# controller.net
KiCad netlist of a schematic drawn in EAGLE
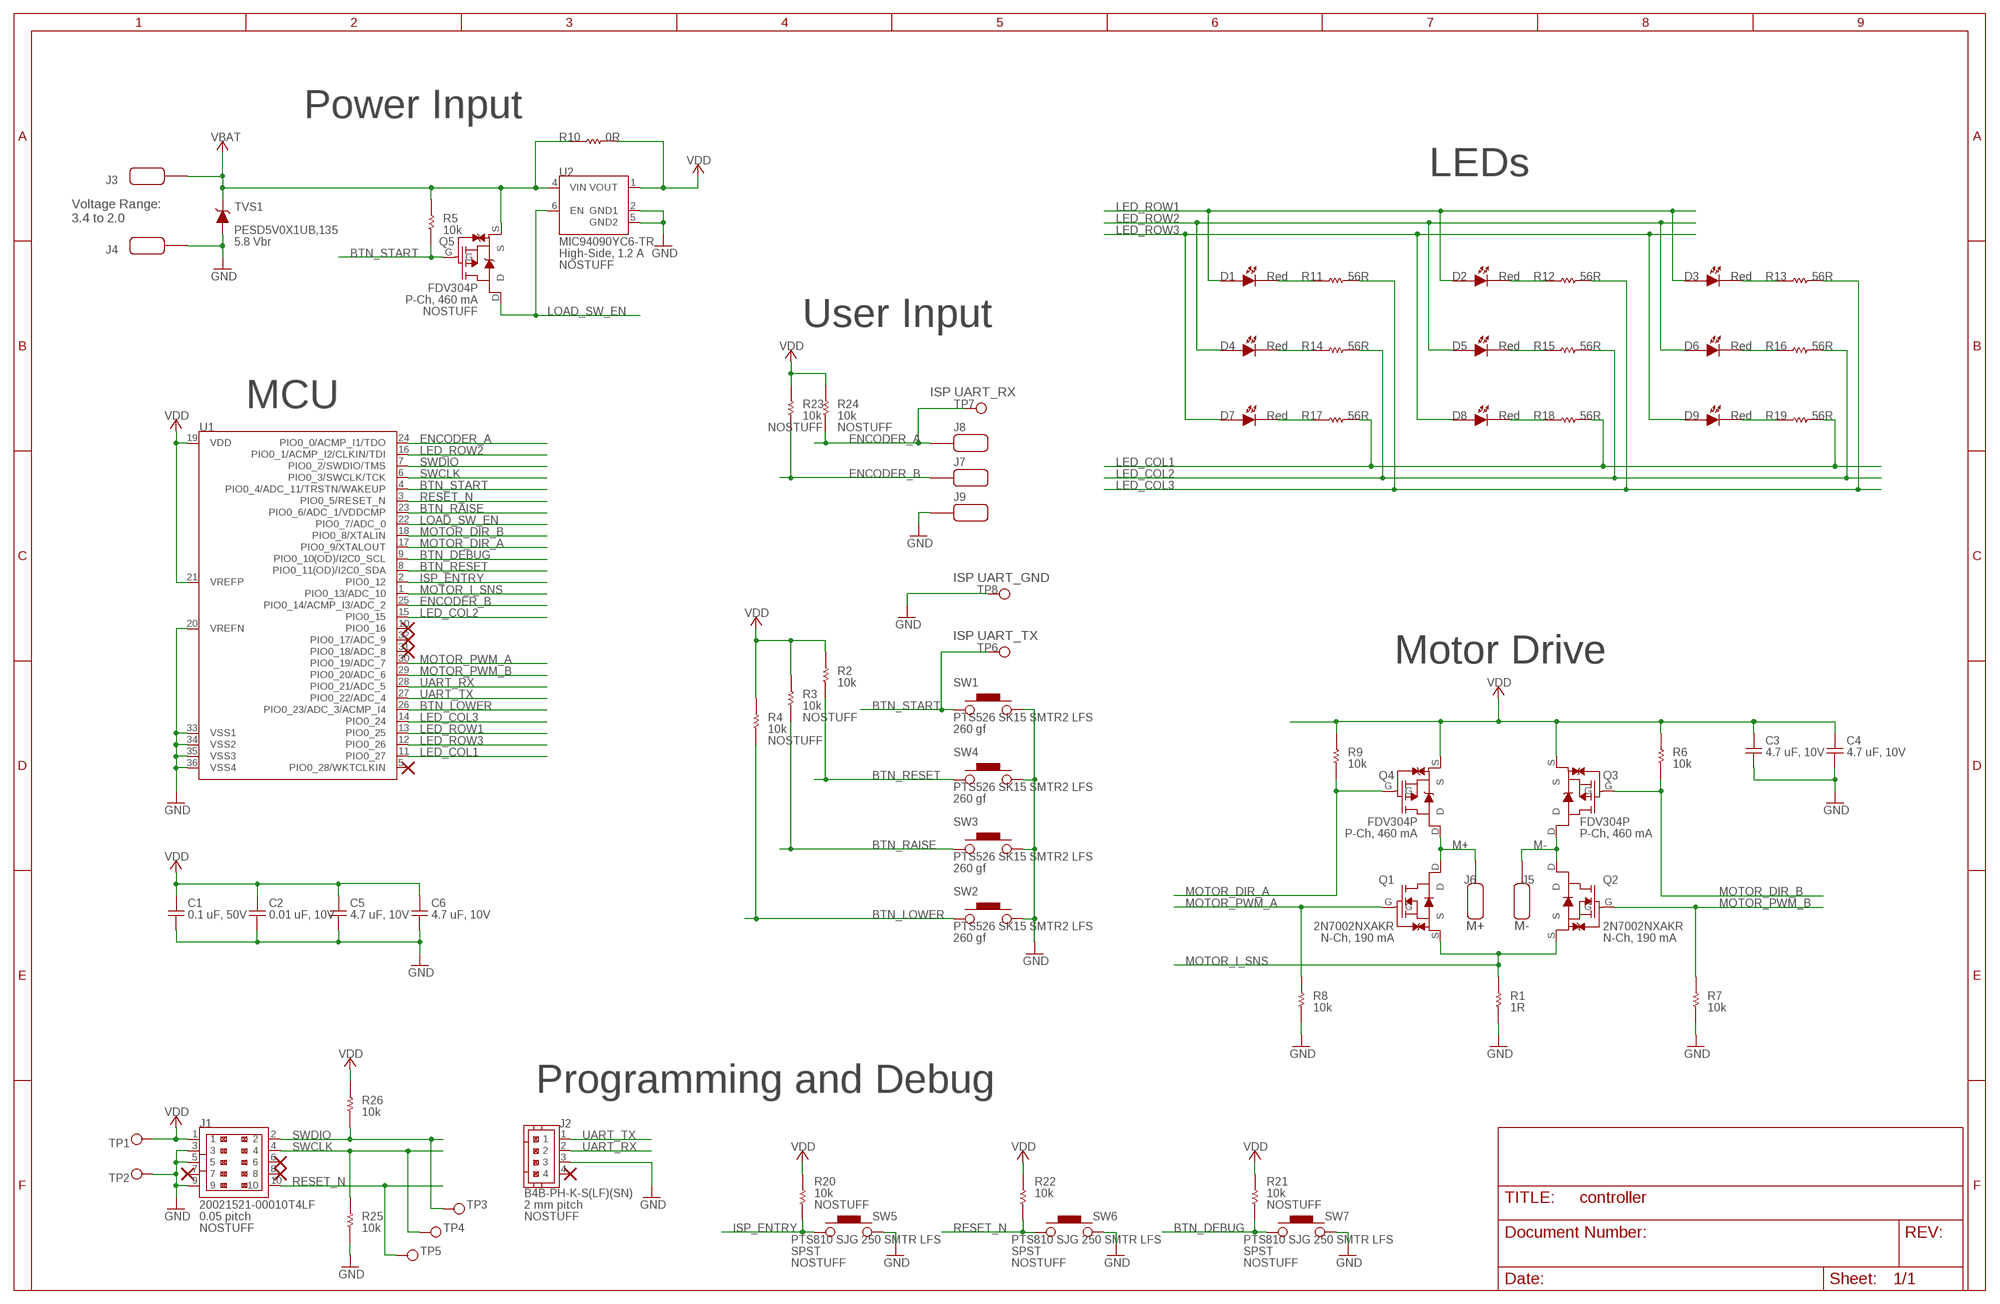
[diagram p0: schematic, sheet 1]

(export (version "E")
  (design (tool "Eeschema 10.0.6"))
  (components
    (comp (ref "C1")
      (value "CAP_C1608X7R1H104K080AA")
      (footprint "eagle-import:CAP_0603")
      (fields
        (field (name "DISPLAY") "0.1 uF, 50V")
        (field (name "DIST_PART_NO") "445-1314-1-ND")
        (field (name "MFG") "TDK")
        (field (name "MFG_PART_NO") "C1608X7R1H104K080AA")
      )
      (libsource (lib "eagle-import") (part "CAP_C1608X7R1H104K080AA"))
    )
    (comp (ref "C2")
      (value "CAP_CL10B103KB8NNNC")
      (footprint "eagle-import:CAP_0603")
      (fields
        (field (name "DISPLAY") "0.01 uF, 10V")
        (field (name "DIST_PART_NO") "1276-1009-1-ND")
        (field (name "MFG") "Samsung")
        (field (name "MFG_PART_NO") "CL10B103KB8NNNC")
      )
      (libsource (lib "eagle-import") (part "CAP_CL10B103KB8NNNC"))
    )
    (comp (ref "C3")
      (value "CAP_CGB3B1X5R1A475M055AC")
      (footprint "eagle-import:CAP_0603")
      (fields
        (field (name "DISPLAY") "4.7 uF, 10V")
        (field (name "DIST_PART_NO") "445-7483-1-ND")
        (field (name "MFG") "TDK")
        (field (name "MFG_PART_NO") "CGB3B1X5R1A475M055AC")
      )
      (libsource (lib "eagle-import") (part "CAP_CGB3B1X5R1A475M055AC"))
    )
    (comp (ref "C4")
      (value "CAP_CGB3B1X5R1A475M055AC")
      (footprint "eagle-import:CAP_0603")
      (fields
        (field (name "DISPLAY") "4.7 uF, 10V")
        (field (name "DIST_PART_NO") "445-7483-1-ND")
        (field (name "MFG") "TDK")
        (field (name "MFG_PART_NO") "CGB3B1X5R1A475M055AC")
      )
      (libsource (lib "eagle-import") (part "CAP_CGB3B1X5R1A475M055AC"))
    )
    (comp (ref "C5")
      (value "CAP_CGB3B1X5R1A475M055AC")
      (footprint "eagle-import:CAP_0603")
      (fields
        (field (name "DISPLAY") "4.7 uF, 10V")
        (field (name "DIST_PART_NO") "445-7483-1-ND")
        (field (name "MFG") "TDK")
        (field (name "MFG_PART_NO") "CGB3B1X5R1A475M055AC")
      )
      (libsource (lib "eagle-import") (part "CAP_CGB3B1X5R1A475M055AC"))
    )
    (comp (ref "C6")
      (value "CAP_CGB3B1X5R1A475M055AC")
      (footprint "eagle-import:CAP_0603")
      (fields
        (field (name "DISPLAY") "4.7 uF, 10V")
        (field (name "DIST_PART_NO") "445-7483-1-ND")
        (field (name "MFG") "TDK")
        (field (name "MFG_PART_NO") "CGB3B1X5R1A475M055AC")
      )
      (libsource (lib "eagle-import") (part "CAP_CGB3B1X5R1A475M055AC"))
    )
    (comp (ref "D1")
      (value "LED_150060RS75000")
      (footprint "eagle-import:LED_0603")
      (fields
        (field (name "DISPLAY") "Red")
        (field (name "DIST_PART_NO") "732-4978-1-ND")
        (field (name "MFG") "Wurth Elektronik")
        (field (name "MFG_PART_NO") "150060RS75000")
      )
      (libsource (lib "eagle-import") (part "LED_150060RS75000"))
    )
    (comp (ref "D2")
      (value "LED_150060RS75000")
      (footprint "eagle-import:LED_0603")
      (fields
        (field (name "DISPLAY") "Red")
        (field (name "DIST_PART_NO") "732-4978-1-ND")
        (field (name "MFG") "Wurth Elektronik")
        (field (name "MFG_PART_NO") "150060RS75000")
      )
      (libsource (lib "eagle-import") (part "LED_150060RS75000"))
    )
    (comp (ref "D3")
      (value "LED_150060RS75000")
      (footprint "eagle-import:LED_0603")
      (fields
        (field (name "DISPLAY") "Red")
        (field (name "DIST_PART_NO") "732-4978-1-ND")
        (field (name "MFG") "Wurth Elektronik")
        (field (name "MFG_PART_NO") "150060RS75000")
      )
      (libsource (lib "eagle-import") (part "LED_150060RS75000"))
    )
    (comp (ref "D4")
      (value "LED_150060RS75000")
      (footprint "eagle-import:LED_0603")
      (fields
        (field (name "DISPLAY") "Red")
        (field (name "DIST_PART_NO") "732-4978-1-ND")
        (field (name "MFG") "Wurth Elektronik")
        (field (name "MFG_PART_NO") "150060RS75000")
      )
      (libsource (lib "eagle-import") (part "LED_150060RS75000"))
    )
    (comp (ref "D5")
      (value "LED_150060RS75000")
      (footprint "eagle-import:LED_0603")
      (fields
        (field (name "DISPLAY") "Red")
        (field (name "DIST_PART_NO") "732-4978-1-ND")
        (field (name "MFG") "Wurth Elektronik")
        (field (name "MFG_PART_NO") "150060RS75000")
      )
      (libsource (lib "eagle-import") (part "LED_150060RS75000"))
    )
    (comp (ref "D6")
      (value "LED_150060RS75000")
      (footprint "eagle-import:LED_0603")
      (fields
        (field (name "DISPLAY") "Red")
        (field (name "DIST_PART_NO") "732-4978-1-ND")
        (field (name "MFG") "Wurth Elektronik")
        (field (name "MFG_PART_NO") "150060RS75000")
      )
      (libsource (lib "eagle-import") (part "LED_150060RS75000"))
    )
    (comp (ref "D7")
      (value "LED_150060RS75000")
      (footprint "eagle-import:LED_0603")
      (fields
        (field (name "DISPLAY") "Red")
        (field (name "DIST_PART_NO") "732-4978-1-ND")
        (field (name "MFG") "Wurth Elektronik")
        (field (name "MFG_PART_NO") "150060RS75000")
      )
      (libsource (lib "eagle-import") (part "LED_150060RS75000"))
    )
    (comp (ref "D8")
      (value "LED_150060RS75000")
      (footprint "eagle-import:LED_0603")
      (fields
        (field (name "DISPLAY") "Red")
        (field (name "DIST_PART_NO") "732-4978-1-ND")
        (field (name "MFG") "Wurth Elektronik")
        (field (name "MFG_PART_NO") "150060RS75000")
      )
      (libsource (lib "eagle-import") (part "LED_150060RS75000"))
    )
    (comp (ref "D9")
      (value "LED_150060RS75000")
      (footprint "eagle-import:LED_0603")
      (fields
        (field (name "DISPLAY") "Red")
        (field (name "DIST_PART_NO") "732-4978-1-ND")
        (field (name "MFG") "Wurth Elektronik")
        (field (name "MFG_PART_NO") "150060RS75000")
      )
      (libsource (lib "eagle-import") (part "LED_150060RS75000"))
    )
    (comp (ref "J1")
      (value "20021521-00010T4LF")
      (footprint "eagle-import:HEADER_2X5_50MIL_SHROUDED_KEYED")
      (fields
        (field (name "MFG_PART_NO") "20021521-00010T4LF")
        (field (name "DISPLAY") "0.05 pitch")
        (field (name "DIST_PART_NO") "609-6534-ND")
        (field (name "MFG") "Amphenol")
        (field (name "NOSTUFF") "NOSTUFF")
      )
      (libsource (lib "eagle-import") (part "20021521-00010T4LF"))
    )
    (comp (ref "J2")
      (value "B4B-PH-K-S")
      (footprint "eagle-import:JST-PH_2MM_TH")
      (fields
        (field (name "MFG_PART_NO") "B4B-PH-K-S(LF)(SN)")
        (field (name "DISPLAY") "2 mm pitch")
        (field (name "DIST_PART_NO") "455-1706-ND")
        (field (name "MFG") "JST")
        (field (name "NOSTUFF") "NOSTUFF")
      )
      (libsource (lib "eagle-import") (part "B4B-PH-K-S"))
    )
    (comp (ref "J3")
      (value "PAD_1P4X3P25MM")
      (footprint "eagle-import:PAD_1P4MM_X_3P25MM")
      (libsource (lib "eagle-import") (part "PAD_1P4X3P25MM"))
    )
    (comp (ref "J4")
      (value "PAD_1P4X3P25MM")
      (footprint "eagle-import:PAD_1P4MM_X_3P25MM")
      (libsource (lib "eagle-import") (part "PAD_1P4X3P25MM"))
    )
    (comp (ref "J5")
      (value "PAD_1P4X3P25MM")
      (footprint "eagle-import:PAD_1P4MM_X_3P25MM")
      (libsource (lib "eagle-import") (part "PAD_1P4X3P25MM"))
    )
    (comp (ref "J6")
      (value "PAD_1P4X3P25MM")
      (footprint "eagle-import:PAD_1P4MM_X_3P25MM")
      (libsource (lib "eagle-import") (part "PAD_1P4X3P25MM"))
    )
    (comp (ref "J7")
      (value "PAD_1P4X3P25MM")
      (footprint "eagle-import:PAD_1P4MM_X_3P25MM")
      (libsource (lib "eagle-import") (part "PAD_1P4X3P25MM"))
    )
    (comp (ref "J8")
      (value "PAD_1P4X3P25MM")
      (footprint "eagle-import:PAD_1P4MM_X_3P25MM")
      (libsource (lib "eagle-import") (part "PAD_1P4X3P25MM"))
    )
    (comp (ref "J9")
      (value "PAD_1P4X3P25MM")
      (footprint "eagle-import:PAD_1P4MM_X_3P25MM")
      (libsource (lib "eagle-import") (part "PAD_1P4X3P25MM"))
    )
    (comp (ref "Q1")
      (value "2N7002NXAKR")
      (footprint "eagle-import:SOT-23_FET_GENERIC")
      (fields
        (field (name "DISPLAY") "N-Ch, 190 mA")
        (field (name "MFG_PART_NO") "2N7002NXAKR")
        (field (name "DIST_PART_NO") "1727-8643-1-ND")
        (field (name "MFG") "Nexperia")
      )
      (libsource (lib "eagle-import") (part "2N7002NXAKR"))
    )
    (comp (ref "Q2")
      (value "2N7002NXAKR")
      (footprint "eagle-import:SOT-23_FET_GENERIC")
      (fields
        (field (name "DISPLAY") "N-Ch, 190 mA")
        (field (name "MFG_PART_NO") "2N7002NXAKR")
        (field (name "DIST_PART_NO") "1727-8643-1-ND")
        (field (name "MFG") "Nexperia")
      )
      (libsource (lib "eagle-import") (part "2N7002NXAKR"))
    )
    (comp (ref "Q3")
      (value "FDV304P")
      (footprint "eagle-import:SOT-23_FET_GENERIC")
      (fields
        (field (name "DISPLAY") "P-Ch, 460 mA")
        (field (name "MFG_PART_NO") "FDV304P")
        (field (name "DIST_PART_NO") "FDV304PCT-ND")
        (field (name "MFG") "On Semi")
      )
      (libsource (lib "eagle-import") (part "FDV304P"))
    )
    (comp (ref "Q4")
      (value "FDV304P")
      (footprint "eagle-import:SOT-23_FET_GENERIC")
      (fields
        (field (name "DISPLAY") "P-Ch, 460 mA")
        (field (name "MFG_PART_NO") "FDV304P")
        (field (name "DIST_PART_NO") "FDV304PCT-ND")
        (field (name "MFG") "On Semi")
      )
      (libsource (lib "eagle-import") (part "FDV304P"))
    )
    (comp (ref "Q5")
      (value "FDV304P")
      (footprint "eagle-import:SOT-23_FET_GENERIC")
      (fields
        (field (name "DISPLAY") "P-Ch, 460 mA")
        (field (name "MFG_PART_NO") "FDV304P")
        (field (name "DIST_PART_NO") "FDV304PCT-ND")
        (field (name "MFG") "On Semi")
        (field (name "NOSTUFF") "NOSTUFF")
      )
      (libsource (lib "eagle-import") (part "FDV304P"))
    )
    (comp (ref "R1")
      (value "RES_1R_RMCF0603FT1R00")
      (footprint "eagle-import:RES_0603")
      (fields
        (field (name "DISPLAY") "1R")
        (field (name "DIST_PART_NO") "RMCF0603FT1R00CT-ND")
        (field (name "MFG") "Stackpole")
        (field (name "MFG_PART_NO") "RMCF0603FT1R00")
      )
      (libsource (lib "eagle-import") (part "RES_1R_RMCF0603FT1R00"))
    )
    (comp (ref "R2")
      (value "RES_10K_RC0603FR-0710KL")
      (footprint "eagle-import:RES_0603")
      (fields
        (field (name "DISPLAY") "10k")
        (field (name "DIST_PART_NO") "311-10.0KHRCT-ND")
        (field (name "MFG") "Yageo")
        (field (name "MFG_PART_NO") "RC0603FR-0710KL")
      )
      (libsource (lib "eagle-import") (part "RES_10K_RC0603FR-0710KL"))
    )
    (comp (ref "R3")
      (value "RES_10K_RC0603FR-0710KL")
      (footprint "eagle-import:RES_0603")
      (fields
        (field (name "DISPLAY") "10k")
        (field (name "DIST_PART_NO") "311-10.0KHRCT-ND")
        (field (name "MFG") "Yageo")
        (field (name "MFG_PART_NO") "RC0603FR-0710KL")
        (field (name "NOSTUFF") "NOSTUFF")
      )
      (libsource (lib "eagle-import") (part "RES_10K_RC0603FR-0710KL"))
    )
    (comp (ref "R4")
      (value "RES_10K_RC0603FR-0710KL")
      (footprint "eagle-import:RES_0603")
      (fields
        (field (name "DISPLAY") "10k")
        (field (name "DIST_PART_NO") "311-10.0KHRCT-ND")
        (field (name "MFG") "Yageo")
        (field (name "MFG_PART_NO") "RC0603FR-0710KL")
        (field (name "NOSTUFF") "NOSTUFF")
      )
      (libsource (lib "eagle-import") (part "RES_10K_RC0603FR-0710KL"))
    )
    (comp (ref "R5")
      (value "RES_10K_RC0603FR-0710KL")
      (footprint "eagle-import:RES_0603")
      (fields
        (field (name "DISPLAY") "10k")
        (field (name "DIST_PART_NO") "311-10.0KHRCT-ND")
        (field (name "MFG") "Yageo")
        (field (name "MFG_PART_NO") "RC0603FR-0710KL")
      )
      (libsource (lib "eagle-import") (part "RES_10K_RC0603FR-0710KL"))
    )
    (comp (ref "R6")
      (value "RES_10K_RC0603FR-0710KL")
      (footprint "eagle-import:RES_0603")
      (fields
        (field (name "DISPLAY") "10k")
        (field (name "DIST_PART_NO") "311-10.0KHRCT-ND")
        (field (name "MFG") "Yageo")
        (field (name "MFG_PART_NO") "RC0603FR-0710KL")
      )
      (libsource (lib "eagle-import") (part "RES_10K_RC0603FR-0710KL"))
    )
    (comp (ref "R7")
      (value "RES_10K_RC0603FR-0710KL")
      (footprint "eagle-import:RES_0603")
      (fields
        (field (name "DISPLAY") "10k")
        (field (name "DIST_PART_NO") "311-10.0KHRCT-ND")
        (field (name "MFG") "Yageo")
        (field (name "MFG_PART_NO") "RC0603FR-0710KL")
      )
      (libsource (lib "eagle-import") (part "RES_10K_RC0603FR-0710KL"))
    )
    (comp (ref "R8")
      (value "RES_10K_RC0603FR-0710KL")
      (footprint "eagle-import:RES_0603")
      (fields
        (field (name "DISPLAY") "10k")
        (field (name "DIST_PART_NO") "311-10.0KHRCT-ND")
        (field (name "MFG") "Yageo")
        (field (name "MFG_PART_NO") "RC0603FR-0710KL")
      )
      (libsource (lib "eagle-import") (part "RES_10K_RC0603FR-0710KL"))
    )
    (comp (ref "R9")
      (value "RES_10K_RC0603FR-0710KL")
      (footprint "eagle-import:RES_0603")
      (fields
        (field (name "DISPLAY") "10k")
        (field (name "DIST_PART_NO") "311-10.0KHRCT-ND")
        (field (name "MFG") "Yageo")
        (field (name "MFG_PART_NO") "RC0603FR-0710KL")
      )
      (libsource (lib "eagle-import") (part "RES_10K_RC0603FR-0710KL"))
    )
    (comp (ref "R10")
      (value "RES_0R_RC0603JR-070RL")
      (footprint "eagle-import:RES_0603")
      (fields
        (field (name "DISPLAY") "0R")
        (field (name "DIST_PART_NO") "311-0.0GRCT-ND")
        (field (name "MFG") "Yageo")
        (field (name "MFG_PART_NO") "RC0603JR-070RL")
      )
      (libsource (lib "eagle-import") (part "RES_0R_RC0603JR-070RL"))
    )
    (comp (ref "R11")
      (value "RES_56R_RC0603FR-0756RL")
      (footprint "eagle-import:RES_0603")
      (fields
        (field (name "DISPLAY") "56R")
        (field (name "DIST_PART_NO") "311-56.0HRCT-ND")
        (field (name "MFG") "Yageo")
        (field (name "MFG_PART_NO") "RC0603FR-0756RL")
      )
      (libsource (lib "eagle-import") (part "RES_56R_RC0603FR-0756RL"))
    )
    (comp (ref "R12")
      (value "RES_56R_RC0603FR-0756RL")
      (footprint "eagle-import:RES_0603")
      (fields
        (field (name "DISPLAY") "56R")
        (field (name "DIST_PART_NO") "311-56.0HRCT-ND")
        (field (name "MFG") "Yageo")
        (field (name "MFG_PART_NO") "RC0603FR-0756RL")
      )
      (libsource (lib "eagle-import") (part "RES_56R_RC0603FR-0756RL"))
    )
    (comp (ref "R13")
      (value "RES_56R_RC0603FR-0756RL")
      (footprint "eagle-import:RES_0603")
      (fields
        (field (name "DISPLAY") "56R")
        (field (name "DIST_PART_NO") "311-56.0HRCT-ND")
        (field (name "MFG") "Yageo")
        (field (name "MFG_PART_NO") "RC0603FR-0756RL")
      )
      (libsource (lib "eagle-import") (part "RES_56R_RC0603FR-0756RL"))
    )
    (comp (ref "R14")
      (value "RES_56R_RC0603FR-0756RL")
      (footprint "eagle-import:RES_0603")
      (fields
        (field (name "DISPLAY") "56R")
        (field (name "DIST_PART_NO") "311-56.0HRCT-ND")
        (field (name "MFG") "Yageo")
        (field (name "MFG_PART_NO") "RC0603FR-0756RL")
      )
      (libsource (lib "eagle-import") (part "RES_56R_RC0603FR-0756RL"))
    )
    (comp (ref "R15")
      (value "RES_56R_RC0603FR-0756RL")
      (footprint "eagle-import:RES_0603")
      (fields
        (field (name "DISPLAY") "56R")
        (field (name "DIST_PART_NO") "311-56.0HRCT-ND")
        (field (name "MFG") "Yageo")
        (field (name "MFG_PART_NO") "RC0603FR-0756RL")
      )
      (libsource (lib "eagle-import") (part "RES_56R_RC0603FR-0756RL"))
    )
    (comp (ref "R16")
      (value "RES_56R_RC0603FR-0756RL")
      (footprint "eagle-import:RES_0603")
      (fields
        (field (name "DISPLAY") "56R")
        (field (name "DIST_PART_NO") "311-56.0HRCT-ND")
        (field (name "MFG") "Yageo")
        (field (name "MFG_PART_NO") "RC0603FR-0756RL")
      )
      (libsource (lib "eagle-import") (part "RES_56R_RC0603FR-0756RL"))
    )
    (comp (ref "R17")
      (value "RES_56R_RC0603FR-0756RL")
      (footprint "eagle-import:RES_0603")
      (fields
        (field (name "DISPLAY") "56R")
        (field (name "DIST_PART_NO") "311-56.0HRCT-ND")
        (field (name "MFG") "Yageo")
        (field (name "MFG_PART_NO") "RC0603FR-0756RL")
      )
      (libsource (lib "eagle-import") (part "RES_56R_RC0603FR-0756RL"))
    )
    (comp (ref "R18")
      (value "RES_56R_RC0603FR-0756RL")
      (footprint "eagle-import:RES_0603")
      (fields
        (field (name "DISPLAY") "56R")
        (field (name "DIST_PART_NO") "311-56.0HRCT-ND")
        (field (name "MFG") "Yageo")
        (field (name "MFG_PART_NO") "RC0603FR-0756RL")
      )
      (libsource (lib "eagle-import") (part "RES_56R_RC0603FR-0756RL"))
    )
    (comp (ref "R19")
      (value "RES_56R_RC0603FR-0756RL")
      (footprint "eagle-import:RES_0603")
      (fields
        (field (name "DISPLAY") "56R")
        (field (name "DIST_PART_NO") "311-56.0HRCT-ND")
        (field (name "MFG") "Yageo")
        (field (name "MFG_PART_NO") "RC0603FR-0756RL")
      )
      (libsource (lib "eagle-import") (part "RES_56R_RC0603FR-0756RL"))
    )
    (comp (ref "R20")
      (value "RES_10K_RC0603FR-0710KL")
      (footprint "eagle-import:RES_0603")
      (fields
        (field (name "DISPLAY") "10k")
        (field (name "DIST_PART_NO") "311-10.0KHRCT-ND")
        (field (name "MFG") "Yageo")
        (field (name "MFG_PART_NO") "RC0603FR-0710KL")
        (field (name "NOSTUFF") "NOSTUFF")
      )
      (libsource (lib "eagle-import") (part "RES_10K_RC0603FR-0710KL"))
    )
    (comp (ref "R21")
      (value "RES_10K_RC0603FR-0710KL")
      (footprint "eagle-import:RES_0603")
      (fields
        (field (name "DISPLAY") "10k")
        (field (name "DIST_PART_NO") "311-10.0KHRCT-ND")
        (field (name "MFG") "Yageo")
        (field (name "MFG_PART_NO") "RC0603FR-0710KL")
        (field (name "NOSTUFF") "NOSTUFF")
      )
      (libsource (lib "eagle-import") (part "RES_10K_RC0603FR-0710KL"))
    )
    (comp (ref "R22")
      (value "RES_10K_RC0603FR-0710KL")
      (footprint "eagle-import:RES_0603")
      (fields
        (field (name "DISPLAY") "10k")
        (field (name "DIST_PART_NO") "311-10.0KHRCT-ND")
        (field (name "MFG") "Yageo")
        (field (name "MFG_PART_NO") "RC0603FR-0710KL")
      )
      (libsource (lib "eagle-import") (part "RES_10K_RC0603FR-0710KL"))
    )
    (comp (ref "R23")
      (value "RES_10K_RC0603FR-0710KL")
      (footprint "eagle-import:RES_0603")
      (fields
        (field (name "DISPLAY") "10k")
        (field (name "DIST_PART_NO") "311-10.0KHRCT-ND")
        (field (name "MFG") "Yageo")
        (field (name "MFG_PART_NO") "RC0603FR-0710KL")
        (field (name "NOSTUFF") "NOSTUFF")
      )
      (libsource (lib "eagle-import") (part "RES_10K_RC0603FR-0710KL"))
    )
    (comp (ref "R24")
      (value "RES_10K_RC0603FR-0710KL")
      (footprint "eagle-import:RES_0603")
      (fields
        (field (name "DISPLAY") "10k")
        (field (name "DIST_PART_NO") "311-10.0KHRCT-ND")
        (field (name "MFG") "Yageo")
        (field (name "MFG_PART_NO") "RC0603FR-0710KL")
        (field (name "NOSTUFF") "NOSTUFF")
      )
      (libsource (lib "eagle-import") (part "RES_10K_RC0603FR-0710KL"))
    )
    (comp (ref "R25")
      (value "RES_10K_RC0603FR-0710KL")
      (footprint "eagle-import:RES_0603")
      (fields
        (field (name "DISPLAY") "10k")
        (field (name "DIST_PART_NO") "311-10.0KHRCT-ND")
        (field (name "MFG") "Yageo")
        (field (name "MFG_PART_NO") "RC0603FR-0710KL")
      )
      (libsource (lib "eagle-import") (part "RES_10K_RC0603FR-0710KL"))
    )
    (comp (ref "R26")
      (value "RES_10K_RC0603FR-0710KL")
      (footprint "eagle-import:RES_0603")
      (fields
        (field (name "DISPLAY") "10k")
        (field (name "DIST_PART_NO") "311-10.0KHRCT-ND")
        (field (name "MFG") "Yageo")
        (field (name "MFG_PART_NO") "RC0603FR-0710KL")
      )
      (libsource (lib "eagle-import") (part "RES_10K_RC0603FR-0710KL"))
    )
    (comp (ref "SW1")
      (value "PTS526_SK15_SMTR2_LFS")
      (footprint "eagle-import:PTS526-G_LEAD")
      (fields
        (field (name "MFG_PART_NO") "PTS526 SK15 SMTR2 LFS")
        (field (name "DISPLAY") "260 gf")
        (field (name "DIST_PART_NO") "CKN12221-1-ND")
        (field (name "MFG") "C and K")
      )
      (libsource (lib "eagle-import") (part "PTS526_SK15_SMTR2_LFS"))
    )
    (comp (ref "SW2")
      (value "PTS526_SK15_SMTR2_LFS")
      (footprint "eagle-import:PTS526-G_LEAD")
      (fields
        (field (name "MFG_PART_NO") "PTS526 SK15 SMTR2 LFS")
        (field (name "DISPLAY") "260 gf")
        (field (name "DIST_PART_NO") "CKN12221-1-ND")
        (field (name "MFG") "C and K")
      )
      (libsource (lib "eagle-import") (part "PTS526_SK15_SMTR2_LFS"))
    )
    (comp (ref "SW3")
      (value "PTS526_SK15_SMTR2_LFS")
      (footprint "eagle-import:PTS526-G_LEAD")
      (fields
        (field (name "MFG_PART_NO") "PTS526 SK15 SMTR2 LFS")
        (field (name "DISPLAY") "260 gf")
        (field (name "DIST_PART_NO") "CKN12221-1-ND")
        (field (name "MFG") "C and K")
      )
      (libsource (lib "eagle-import") (part "PTS526_SK15_SMTR2_LFS"))
    )
    (comp (ref "SW4")
      (value "PTS526_SK15_SMTR2_LFS")
      (footprint "eagle-import:PTS526-G_LEAD")
      (fields
        (field (name "MFG_PART_NO") "PTS526 SK15 SMTR2 LFS")
        (field (name "DISPLAY") "260 gf")
        (field (name "DIST_PART_NO") "CKN12221-1-ND")
        (field (name "MFG") "C and K")
      )
      (libsource (lib "eagle-import") (part "PTS526_SK15_SMTR2_LFS"))
    )
    (comp (ref "SW5")
      (value "PTS810_SJG_250_SMTR_LFS")
      (footprint "eagle-import:PTS810")
      (fields
        (field (name "MFG_PART_NO") "PTS810 SJG 250 SMTR LFS")
        (field (name "DISPLAY") "SPST")
        (field (name "DIST_PART_NO") "CKN10504CT-ND")
        (field (name "MFG") "C and K")
        (field (name "NOSTUFF") "NOSTUFF")
      )
      (libsource (lib "eagle-import") (part "PTS810_SJG_250_SMTR_LFS"))
    )
    (comp (ref "SW6")
      (value "PTS810_SJG_250_SMTR_LFS")
      (footprint "eagle-import:PTS810")
      (fields
        (field (name "MFG_PART_NO") "PTS810 SJG 250 SMTR LFS")
        (field (name "DISPLAY") "SPST")
        (field (name "DIST_PART_NO") "CKN10504CT-ND")
        (field (name "MFG") "C and K")
        (field (name "NOSTUFF") "NOSTUFF")
      )
      (libsource (lib "eagle-import") (part "PTS810_SJG_250_SMTR_LFS"))
    )
    (comp (ref "SW7")
      (value "PTS810_SJG_250_SMTR_LFS")
      (footprint "eagle-import:PTS810")
      (fields
        (field (name "MFG_PART_NO") "PTS810 SJG 250 SMTR LFS")
        (field (name "DISPLAY") "SPST")
        (field (name "DIST_PART_NO") "CKN10504CT-ND")
        (field (name "MFG") "C and K")
        (field (name "NOSTUFF") "NOSTUFF")
      )
      (libsource (lib "eagle-import") (part "PTS810_SJG_250_SMTR_LFS"))
    )
    (comp (ref "TP1")
      (value "TP_1P6_MM_ROUND")
      (footprint "eagle-import:TP_1P6_MM_ROUND")
      (libsource (lib "eagle-import") (part "TP_1P6_MM_ROUND"))
    )
    (comp (ref "TP2")
      (value "TP_1P6_MM_ROUND")
      (footprint "eagle-import:TP_1P6_MM_ROUND")
      (libsource (lib "eagle-import") (part "TP_1P6_MM_ROUND"))
    )
    (comp (ref "TP3")
      (value "TP_1P6_MM_ROUND")
      (footprint "eagle-import:TP_1P6_MM_ROUND")
      (libsource (lib "eagle-import") (part "TP_1P6_MM_ROUND"))
    )
    (comp (ref "TP4")
      (value "TP_1P6_MM_ROUND")
      (footprint "eagle-import:TP_1P6_MM_ROUND")
      (libsource (lib "eagle-import") (part "TP_1P6_MM_ROUND"))
    )
    (comp (ref "TP5")
      (value "TP_1P6_MM_ROUND")
      (footprint "eagle-import:TP_1P6_MM_ROUND")
      (libsource (lib "eagle-import") (part "TP_1P6_MM_ROUND"))
    )
    (comp (ref "TP6")
      (value "TP_1P6_MM_ROUND")
      (footprint "eagle-import:TP_1P6_MM_ROUND")
      (libsource (lib "eagle-import") (part "TP_1P6_MM_ROUND"))
    )
    (comp (ref "TP7")
      (value "TP_1P6_MM_ROUND")
      (footprint "eagle-import:TP_1P6_MM_ROUND")
      (libsource (lib "eagle-import") (part "TP_1P6_MM_ROUND"))
    )
    (comp (ref "TP8")
      (value "TP_1P6_MM_ROUND")
      (footprint "eagle-import:TP_1P6_MM_ROUND")
      (libsource (lib "eagle-import") (part "TP_1P6_MM_ROUND"))
    )
    (comp (ref "TVS1")
      (value "PESD5V0X1UB,135")
      (footprint "eagle-import:SOD523")
      (fields
        (field (name "MFG_PART_NO") "PESD5V0X1UB,135")
        (field (name "DISPLAY") "5.8 Vbr")
        (field (name "DIST_PART_NO") "1727-5906-1-ND")
        (field (name "MFG") "NXP")
      )
      (libsource (lib "eagle-import") (part "PESD5V0X1UB,135"))
    )
    (comp (ref "U1")
      (value "LPC822M101JHI33ELPC82X_VQFN33_HAND_SOLDER")
      (footprint "eagle-import:LPC82X_VQFN33_HAND_SOLDER")
      (fields
        (field (name "MFG_PART_NO") "LPC822M101JHI33E")
        (field (name "DIST_PART_NO") "568-11571-ND")
        (field (name "MFG") "NXP")
      )
      (libsource (lib "eagle-import") (part "LPC822M101JHI33ELPC82X_VQFN33_HAND_SOLDER"))
    )
    (comp (ref "U2")
      (value "MIC94090YC6")
      (footprint "eagle-import:SC-70-6_GENERIC")
      (fields
        (field (name "MFG_PART_NO") "MIC94090YC6-TR")
        (field (name "DISPLAY") "High-Side, 1.2 A")
        (field (name "DIST_PART_NO") "576-3484-1-ND")
        (field (name "MFG") "Micrel")
        (field (name "NOSTUFF") "NOSTUFF")
      )
      (libsource (lib "eagle-import") (part "MIC94090YC6"))
    )
  )
  (nets
    (net (code "1") (name "/BTN_DEBUG") (class "Default")
      (node (ref "R21") (pin "P$1") (pinfunction "P$1_P$1") (pintype "bidirectional"))
      (node (ref "SW7") (pin "P1") (pinfunction "P1_P1") (pintype "bidirectional"))
      (node (ref "U1") (pin "9") (pinfunction "PIO0_10(OD)/I2C0_SCL_9") (pintype "bidirectional"))
    )
    (net (code "2") (name "/BTN_LOWER") (class "Default")
      (node (ref "R4") (pin "P$1") (pinfunction "P$1_P$1") (pintype "bidirectional"))
      (node (ref "SW2") (pin "1") (pinfunction "P1_1") (pintype "bidirectional"))
      (node (ref "U1") (pin "26") (pinfunction "PIO0_23/ADC_3/ACMP_I4_26") (pintype "bidirectional"))
    )
    (net (code "3") (name "/BTN_RAISE") (class "Default")
      (node (ref "R3") (pin "P$1") (pinfunction "P$1_P$1") (pintype "bidirectional"))
      (node (ref "SW3") (pin "1") (pinfunction "P1_1") (pintype "bidirectional"))
      (node (ref "U1") (pin "23") (pinfunction "PIO0_6/ADC_1/VDDCMP_23") (pintype "bidirectional"))
    )
    (net (code "4") (name "/BTN_RESET") (class "Default")
      (node (ref "R2") (pin "P$1") (pinfunction "P$1_P$1") (pintype "bidirectional"))
      (node (ref "SW4") (pin "1") (pinfunction "P1_1") (pintype "bidirectional"))
      (node (ref "U1") (pin "8") (pinfunction "PIO0_11(OD)/I2C0_SDA_8") (pintype "bidirectional"))
    )
    (net (code "5") (name "/BTN_START") (class "Default")
      (node (ref "Q5") (pin "G") (pinfunction "G_G") (pintype "bidirectional"))
      (node (ref "R5") (pin "P$1") (pinfunction "P$1_P$1") (pintype "bidirectional"))
      (node (ref "SW1") (pin "1") (pinfunction "P1_1") (pintype "bidirectional"))
      (node (ref "TP6") (pin "P$1") (pinfunction "P1_P$1") (pintype "bidirectional"))
      (node (ref "U1") (pin "4") (pinfunction "PIO0_4/ADC_11/TRSTN/WAKEUP_4") (pintype "bidirectional"))
    )
    (net (code "6") (name "/ENCODER_A") (class "Default")
      (node (ref "J8") (pin "1") (pinfunction "PAD_1") (pintype "bidirectional"))
      (node (ref "R24") (pin "P$1") (pinfunction "P$1_P$1") (pintype "bidirectional"))
      (node (ref "TP7") (pin "P$1") (pinfunction "P1_P$1") (pintype "bidirectional"))
      (node (ref "U1") (pin "24") (pinfunction "PIO0_0/ACMP_I1/TDO_24") (pintype "bidirectional"))
    )
    (net (code "7") (name "/ENCODER_B") (class "Default")
      (node (ref "J7") (pin "1") (pinfunction "PAD_1") (pintype "bidirectional"))
      (node (ref "R23") (pin "P$1") (pinfunction "P$1_P$1") (pintype "bidirectional"))
      (node (ref "U1") (pin "25") (pinfunction "PIO0_14/ACMP_I3/ADC_2_25") (pintype "bidirectional"))
    )
    (net (code "8") (name "/ISP_ENTRY") (class "Default")
      (node (ref "R20") (pin "P$1") (pinfunction "P$1_P$1") (pintype "bidirectional"))
      (node (ref "SW5") (pin "P1") (pinfunction "P1_P1") (pintype "bidirectional"))
      (node (ref "U1") (pin "2") (pinfunction "PIO0_12_2") (pintype "bidirectional"))
    )
    (net (code "9") (name "/LED_COL1") (class "Default")
      (node (ref "R17") (pin "P$2") (pinfunction "P$2_P$2") (pintype "bidirectional"))
      (node (ref "R18") (pin "P$2") (pinfunction "P$2_P$2") (pintype "bidirectional"))
      (node (ref "R19") (pin "P$2") (pinfunction "P$2_P$2") (pintype "bidirectional"))
      (node (ref "U1") (pin "11") (pinfunction "PIO0_27_11") (pintype "bidirectional"))
    )
    (net (code "10") (name "/LED_COL2") (class "Default")
      (node (ref "R14") (pin "P$2") (pinfunction "P$2_P$2") (pintype "bidirectional"))
      (node (ref "R15") (pin "P$2") (pinfunction "P$2_P$2") (pintype "bidirectional"))
      (node (ref "R16") (pin "P$2") (pinfunction "P$2_P$2") (pintype "bidirectional"))
      (node (ref "U1") (pin "15") (pinfunction "PIO0_15_15") (pintype "bidirectional"))
    )
    (net (code "11") (name "/LED_COL3") (class "Default")
      (node (ref "R11") (pin "P$2") (pinfunction "P$2_P$2") (pintype "bidirectional"))
      (node (ref "R12") (pin "P$2") (pinfunction "P$2_P$2") (pintype "bidirectional"))
      (node (ref "R13") (pin "P$2") (pinfunction "P$2_P$2") (pintype "bidirectional"))
      (node (ref "U1") (pin "14") (pinfunction "PIO0_24_14") (pintype "bidirectional"))
    )
    (net (code "12") (name "/LED_ROW1") (class "Default")
      (node (ref "D1") (pin "A") (pinfunction "A_A") (pintype "bidirectional"))
      (node (ref "D2") (pin "A") (pinfunction "A_A") (pintype "bidirectional"))
      (node (ref "D3") (pin "A") (pinfunction "A_A") (pintype "bidirectional"))
      (node (ref "U1") (pin "13") (pinfunction "PIO0_25_13") (pintype "bidirectional"))
    )
    (net (code "13") (name "/LED_ROW2") (class "Default")
      (node (ref "D4") (pin "A") (pinfunction "A_A") (pintype "bidirectional"))
      (node (ref "D5") (pin "A") (pinfunction "A_A") (pintype "bidirectional"))
      (node (ref "D6") (pin "A") (pinfunction "A_A") (pintype "bidirectional"))
      (node (ref "U1") (pin "16") (pinfunction "PIO0_1/ACMP_I2/CLKIN/TDI_16") (pintype "bidirectional"))
    )
    (net (code "14") (name "/LED_ROW3") (class "Default")
      (node (ref "D7") (pin "A") (pinfunction "A_A") (pintype "bidirectional"))
      (node (ref "D8") (pin "A") (pinfunction "A_A") (pintype "bidirectional"))
      (node (ref "D9") (pin "A") (pinfunction "A_A") (pintype "bidirectional"))
      (node (ref "U1") (pin "12") (pinfunction "PIO0_26_12") (pintype "bidirectional"))
    )
    (net (code "15") (name "/LOAD_SW_EN") (class "Default")
      (node (ref "Q5") (pin "D") (pinfunction "D_D") (pintype "bidirectional"))
      (node (ref "U1") (pin "22") (pinfunction "PIO0_7/ADC_0_22") (pintype "bidirectional"))
      (node (ref "U2") (pin "6") (pinfunction "EN_6") (pintype "bidirectional"))
    )
    (net (code "16") (name "/M+") (class "Default")
      (node (ref "J6") (pin "1") (pinfunction "PAD_1") (pintype "bidirectional"))
      (node (ref "Q1") (pin "D") (pinfunction "D_D") (pintype "bidirectional"))
      (node (ref "Q4") (pin "D") (pinfunction "D_D") (pintype "bidirectional"))
    )
    (net (code "17") (name "/M-") (class "Default")
      (node (ref "J5") (pin "1") (pinfunction "PAD_1") (pintype "bidirectional"))
      (node (ref "Q2") (pin "D") (pinfunction "D_D") (pintype "bidirectional"))
      (node (ref "Q3") (pin "D") (pinfunction "D_D") (pintype "bidirectional"))
    )
    (net (code "18") (name "/MOTOR_DIR_A") (class "Default")
      (node (ref "Q4") (pin "G") (pinfunction "G_G") (pintype "bidirectional"))
      (node (ref "R9") (pin "P$1") (pinfunction "P$1_P$1") (pintype "bidirectional"))
      (node (ref "U1") (pin "17") (pinfunction "PIO0_9/XTALOUT_17") (pintype "bidirectional"))
    )
    (net (code "19") (name "/MOTOR_DIR_B") (class "Default")
      (node (ref "Q3") (pin "G") (pinfunction "G_G") (pintype "bidirectional"))
      (node (ref "R6") (pin "P$1") (pinfunction "P$1_P$1") (pintype "bidirectional"))
      (node (ref "U1") (pin "18") (pinfunction "PIO0_8/XTALIN_18") (pintype "bidirectional"))
    )
    (net (code "20") (name "/MOTOR_I_SNS") (class "Default")
      (node (ref "Q1") (pin "S") (pinfunction "S_S") (pintype "bidirectional"))
      (node (ref "Q2") (pin "S") (pinfunction "S_S") (pintype "bidirectional"))
      (node (ref "R1") (pin "P$2") (pinfunction "P$2_P$2") (pintype "bidirectional"))
      (node (ref "U1") (pin "1") (pinfunction "PIO0_13/ADC_10_1") (pintype "bidirectional"))
    )
    (net (code "21") (name "/MOTOR_PWM_A") (class "Default")
      (node (ref "Q1") (pin "G") (pinfunction "G_G") (pintype "bidirectional"))
      (node (ref "R8") (pin "P$2") (pinfunction "P$2_P$2") (pintype "bidirectional"))
      (node (ref "U1") (pin "30") (pinfunction "PIO0_19/ADC_7_30") (pintype "bidirectional"))
    )
    (net (code "22") (name "/MOTOR_PWM_B") (class "Default")
      (node (ref "Q2") (pin "G") (pinfunction "G_G") (pintype "bidirectional"))
      (node (ref "R7") (pin "P$2") (pinfunction "P$2_P$2") (pintype "bidirectional"))
      (node (ref "U1") (pin "29") (pinfunction "PIO0_20/ADC_6_29") (pintype "bidirectional"))
    )
    (net (code "23") (name "/RESET_N") (class "Default")
      (node (ref "J1") (pin "10") (pinfunction "10_10") (pintype "bidirectional"))
      (node (ref "R22") (pin "P$1") (pinfunction "P$1_P$1") (pintype "bidirectional"))
      (node (ref "SW6") (pin "P1") (pinfunction "P1_P1") (pintype "bidirectional"))
      (node (ref "TP5") (pin "P$1") (pinfunction "P1_P$1") (pintype "bidirectional"))
      (node (ref "U1") (pin "3") (pinfunction "PIO0_5/RESET_N_3") (pintype "bidirectional"))
    )
    (net (code "24") (name "/SWCLK") (class "Default")
      (node (ref "J1") (pin "4") (pinfunction "4_4") (pintype "bidirectional"))
      (node (ref "R25") (pin "P$2") (pinfunction "P$2_P$2") (pintype "bidirectional"))
      (node (ref "TP4") (pin "P$1") (pinfunction "P1_P$1") (pintype "bidirectional"))
      (node (ref "U1") (pin "6") (pinfunction "PIO0_3/SWCLK/TCK_6") (pintype "bidirectional"))
    )
    (net (code "25") (name "/SWDIO") (class "Default")
      (node (ref "J1") (pin "2") (pinfunction "2_2") (pintype "bidirectional"))
      (node (ref "R26") (pin "P$1") (pinfunction "P$1_P$1") (pintype "bidirectional"))
      (node (ref "TP3") (pin "P$1") (pinfunction "P1_P$1") (pintype "bidirectional"))
      (node (ref "U1") (pin "7") (pinfunction "PIO0_2/SWDIO/TMS_7") (pintype "bidirectional"))
    )
    (net (code "26") (name "/UART_RX") (class "Default")
      (node (ref "J2") (pin "2") (pinfunction "2_2") (pintype "bidirectional"))
      (node (ref "U1") (pin "28") (pinfunction "PIO0_21/ADC_5_28") (pintype "bidirectional"))
    )
    (net (code "27") (name "/UART_TX") (class "Default")
      (node (ref "J2") (pin "1") (pinfunction "1_1") (pintype "bidirectional"))
      (node (ref "U1") (pin "27") (pinfunction "PIO0_22/ADC_4_27") (pintype "bidirectional"))
    )
    (net (code "28") (name "GND") (class "Default")
      (node (ref "C1") (pin "P$2") (pinfunction "P$2_P$2") (pintype "bidirectional"))
      (node (ref "C2") (pin "P$2") (pinfunction "P$2_P$2") (pintype "bidirectional"))
      (node (ref "C3") (pin "P$2") (pinfunction "P$2_P$2") (pintype "bidirectional"))
      (node (ref "C4") (pin "P$2") (pinfunction "P$2_P$2") (pintype "bidirectional"))
      (node (ref "C5") (pin "P$2") (pinfunction "P$2_P$2") (pintype "bidirectional"))
      (node (ref "C6") (pin "P$2") (pinfunction "P$2_P$2") (pintype "bidirectional"))
      (node (ref "J1") (pin "3") (pinfunction "3_3") (pintype "bidirectional"))
      (node (ref "J1") (pin "5") (pinfunction "5_5") (pintype "bidirectional"))
      (node (ref "J1") (pin "9") (pinfunction "9_9") (pintype "bidirectional"))
      (node (ref "J2") (pin "3") (pinfunction "3_3") (pintype "bidirectional"))
      (node (ref "J4") (pin "1") (pinfunction "PAD_1") (pintype "bidirectional"))
      (node (ref "J9") (pin "1") (pinfunction "PAD_1") (pintype "bidirectional"))
      (node (ref "R1") (pin "P$1") (pinfunction "P$1_P$1") (pintype "bidirectional"))
      (node (ref "R25") (pin "P$1") (pinfunction "P$1_P$1") (pintype "bidirectional"))
      (node (ref "R7") (pin "P$1") (pinfunction "P$1_P$1") (pintype "bidirectional"))
      (node (ref "R8") (pin "P$1") (pinfunction "P$1_P$1") (pintype "bidirectional"))
      (node (ref "SW1") (pin "3") (pinfunction "P2_3") (pintype "bidirectional"))
      (node (ref "SW2") (pin "3") (pinfunction "P2_3") (pintype "bidirectional"))
      (node (ref "SW3") (pin "3") (pinfunction "P2_3") (pintype "bidirectional"))
      (node (ref "SW4") (pin "3") (pinfunction "P2_3") (pintype "bidirectional"))
      (node (ref "SW5") (pin "P3") (pinfunction "P2_P3") (pintype "bidirectional"))
      (node (ref "SW6") (pin "P3") (pinfunction "P2_P3") (pintype "bidirectional"))
      (node (ref "SW7") (pin "P3") (pinfunction "P2_P3") (pintype "bidirectional"))
      (node (ref "TP2") (pin "P$1") (pinfunction "P1_P$1") (pintype "bidirectional"))
      (node (ref "TP8") (pin "P$1") (pinfunction "P1_P$1") (pintype "bidirectional"))
      (node (ref "TVS1") (pin "A") (pinfunction "A_A") (pintype "bidirectional"))
      (node (ref "U1") (pin "20") (pinfunction "VREFN_20") (pintype "bidirectional"))
      (node (ref "U1") (pin "33") (pinfunction "VSS1_33") (pintype "bidirectional"))
      (node (ref "U1") (pin "34") (pinfunction "VSS2_34") (pintype "bidirectional"))
      (node (ref "U1") (pin "35") (pinfunction "VSS3_35") (pintype "bidirectional"))
      (node (ref "U1") (pin "36") (pinfunction "VSS4_36") (pintype "bidirectional"))
      (node (ref "U2") (pin "2") (pinfunction "GND1_2") (pintype "bidirectional"))
      (node (ref "U2") (pin "5") (pinfunction "GND2_5") (pintype "bidirectional"))
    )
    (net (code "29") (name "Net-(D1-PadK)") (class "Default")
      (node (ref "D1") (pin "K") (pinfunction "K_K") (pintype "bidirectional"))
      (node (ref "R11") (pin "P$1") (pinfunction "P$1_P$1") (pintype "bidirectional"))
    )
    (net (code "30") (name "Net-(D2-PadK)") (class "Default")
      (node (ref "D2") (pin "K") (pinfunction "K_K") (pintype "bidirectional"))
      (node (ref "R12") (pin "P$1") (pinfunction "P$1_P$1") (pintype "bidirectional"))
    )
    (net (code "31") (name "Net-(D3-PadK)") (class "Default")
      (node (ref "D3") (pin "K") (pinfunction "K_K") (pintype "bidirectional"))
      (node (ref "R13") (pin "P$1") (pinfunction "P$1_P$1") (pintype "bidirectional"))
    )
    (net (code "32") (name "Net-(D4-PadK)") (class "Default")
      (node (ref "D4") (pin "K") (pinfunction "K_K") (pintype "bidirectional"))
      (node (ref "R14") (pin "P$1") (pinfunction "P$1_P$1") (pintype "bidirectional"))
    )
    (net (code "33") (name "Net-(D5-PadK)") (class "Default")
      (node (ref "D5") (pin "K") (pinfunction "K_K") (pintype "bidirectional"))
      (node (ref "R15") (pin "P$1") (pinfunction "P$1_P$1") (pintype "bidirectional"))
    )
    (net (code "34") (name "Net-(D6-PadK)") (class "Default")
      (node (ref "D6") (pin "K") (pinfunction "K_K") (pintype "bidirectional"))
      (node (ref "R16") (pin "P$1") (pinfunction "P$1_P$1") (pintype "bidirectional"))
    )
    (net (code "35") (name "Net-(D7-PadK)") (class "Default")
      (node (ref "D7") (pin "K") (pinfunction "K_K") (pintype "bidirectional"))
      (node (ref "R17") (pin "P$1") (pinfunction "P$1_P$1") (pintype "bidirectional"))
    )
    (net (code "36") (name "Net-(D8-PadK)") (class "Default")
      (node (ref "D8") (pin "K") (pinfunction "K_K") (pintype "bidirectional"))
      (node (ref "R18") (pin "P$1") (pinfunction "P$1_P$1") (pintype "bidirectional"))
    )
    (net (code "37") (name "Net-(D9-PadK)") (class "Default")
      (node (ref "D9") (pin "K") (pinfunction "K_K") (pintype "bidirectional"))
      (node (ref "R19") (pin "P$1") (pinfunction "P$1_P$1") (pintype "bidirectional"))
    )
    (net (code "38") (name "VBAT") (class "Default")
      (node (ref "J3") (pin "1") (pinfunction "PAD_1") (pintype "bidirectional"))
      (node (ref "Q5") (pin "S") (pinfunction "S_S") (pintype "bidirectional"))
      (node (ref "R10") (pin "P$1") (pinfunction "P$1_P$1") (pintype "bidirectional"))
      (node (ref "R5") (pin "P$2") (pinfunction "P$2_P$2") (pintype "bidirectional"))
      (node (ref "TVS1") (pin "K") (pinfunction "K_K") (pintype "bidirectional"))
      (node (ref "U2") (pin "4") (pinfunction "VIN_4") (pintype "bidirectional"))
    )
    (net (code "39") (name "VDD") (class "Default")
      (node (ref "C1") (pin "P$1") (pinfunction "P$1_P$1") (pintype "bidirectional"))
      (node (ref "C2") (pin "P$1") (pinfunction "P$1_P$1") (pintype "bidirectional"))
      (node (ref "C3") (pin "P$1") (pinfunction "P$1_P$1") (pintype "bidirectional"))
      (node (ref "C4") (pin "P$1") (pinfunction "P$1_P$1") (pintype "bidirectional"))
      (node (ref "C5") (pin "P$1") (pinfunction "P$1_P$1") (pintype "bidirectional"))
      (node (ref "C6") (pin "P$1") (pinfunction "P$1_P$1") (pintype "bidirectional"))
      (node (ref "J1") (pin "1") (pinfunction "1_1") (pintype "bidirectional"))
      (node (ref "Q3") (pin "S") (pinfunction "S_S") (pintype "bidirectional"))
      (node (ref "Q4") (pin "S") (pinfunction "S_S") (pintype "bidirectional"))
      (node (ref "R10") (pin "P$2") (pinfunction "P$2_P$2") (pintype "bidirectional"))
      (node (ref "R2") (pin "P$2") (pinfunction "P$2_P$2") (pintype "bidirectional"))
      (node (ref "R20") (pin "P$2") (pinfunction "P$2_P$2") (pintype "bidirectional"))
      (node (ref "R21") (pin "P$2") (pinfunction "P$2_P$2") (pintype "bidirectional"))
      (node (ref "R22") (pin "P$2") (pinfunction "P$2_P$2") (pintype "bidirectional"))
      (node (ref "R23") (pin "P$2") (pinfunction "P$2_P$2") (pintype "bidirectional"))
      (node (ref "R24") (pin "P$2") (pinfunction "P$2_P$2") (pintype "bidirectional"))
      (node (ref "R26") (pin "P$2") (pinfunction "P$2_P$2") (pintype "bidirectional"))
      (node (ref "R3") (pin "P$2") (pinfunction "P$2_P$2") (pintype "bidirectional"))
      (node (ref "R4") (pin "P$2") (pinfunction "P$2_P$2") (pintype "bidirectional"))
      (node (ref "R6") (pin "P$2") (pinfunction "P$2_P$2") (pintype "bidirectional"))
      (node (ref "R9") (pin "P$2") (pinfunction "P$2_P$2") (pintype "bidirectional"))
      (node (ref "TP1") (pin "P$1") (pinfunction "P1_P$1") (pintype "bidirectional"))
      (node (ref "U1") (pin "19") (pinfunction "VDD_19") (pintype "bidirectional"))
      (node (ref "U1") (pin "21") (pinfunction "VREFP_21") (pintype "bidirectional"))
      (node (ref "U2") (pin "1") (pinfunction "VOUT_1") (pintype "bidirectional"))
    )
    (net (code "40") (name "unconnected-(J1-Pad6)") (class "Default")
      (node (ref "J1") (pin "6") (pinfunction "6_6") (pintype "bidirectional"))
    )
    (net (code "41") (name "unconnected-(J1-Pad7)") (class "Default")
      (node (ref "J1") (pin "7") (pinfunction "7_7") (pintype "bidirectional"))
    )
    (net (code "42") (name "unconnected-(J1-Pad8)") (class "Default")
      (node (ref "J1") (pin "8") (pinfunction "8_8") (pintype "bidirectional"))
    )
    (net (code "43") (name "unconnected-(J2-Pad4)") (class "Default")
      (node (ref "J2") (pin "4") (pinfunction "4_4") (pintype "bidirectional"))
    )
    (net (code "44") (name "unconnected-(U1-PIO0_16-Pad10)") (class "Default")
      (node (ref "U1") (pin "10") (pinfunction "PIO0_16_10") (pintype "bidirectional"))
    )
    (net (code "45") (name "unconnected-(U1-PIO0_17{slash}ADC_9-Pad32)") (class "Default")
      (node (ref "U1") (pin "32") (pinfunction "PIO0_17/ADC_9_32") (pintype "bidirectional"))
    )
    (net (code "46") (name "unconnected-(U1-PIO0_18{slash}ADC_8-Pad31)") (class "Default")
      (node (ref "U1") (pin "31") (pinfunction "PIO0_18/ADC_8_31") (pintype "bidirectional"))
    )
    (net (code "47") (name "unconnected-(U1-PIO0_28{slash}WKTCLKIN-Pad5)") (class "Default")
      (node (ref "U1") (pin "5") (pinfunction "PIO0_28/WKTCLKIN_5") (pintype "bidirectional"))
    )
  )
)
